# SeparationPCB.net
KiCad netlist of a schematic drawn in EAGLE
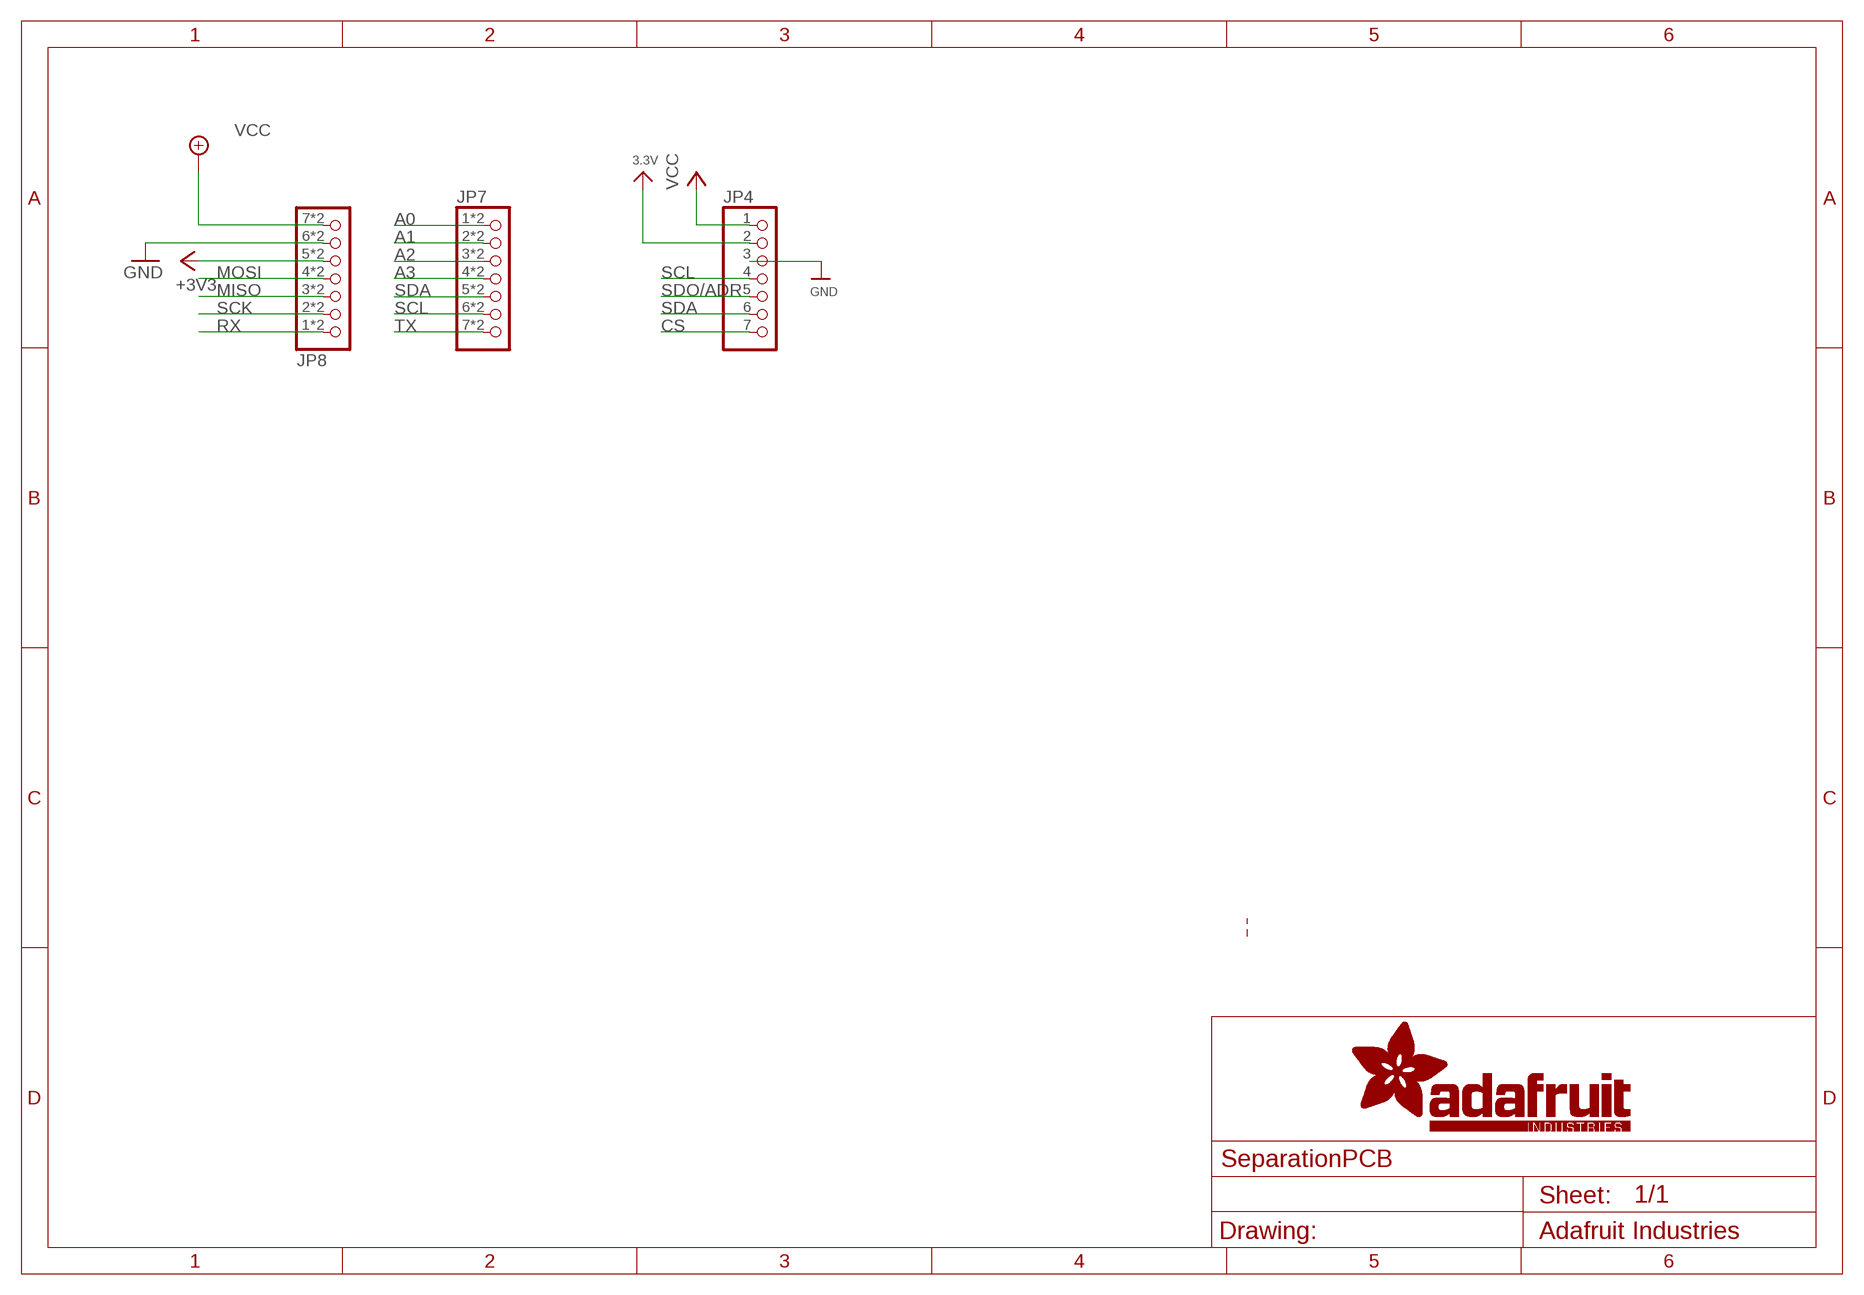
[diagram p0: schematic, sheet 1]

(export (version "E")
  (design (tool "Eeschema 10.0.6"))
  (components
    (comp (ref "JP4")
      (value "HEADER-1X770MIL")
      (footprint "eagle-import:1X07_ROUND_70")
      (libsource (lib "eagle-import") (part "HEADER-1X770MIL"))
    )
    (comp (ref "JP7")
      (value "HEADER-1X7_CASTEL")
      (footprint "eagle-import:1X07_CASTEL")
      (libsource (lib "eagle-import") (part "HEADER-1X7_CASTEL"))
    )
    (comp (ref "JP8")
      (value "HEADER-1X7_CASTEL")
      (footprint "eagle-import:1X07_CASTEL")
      (libsource (lib "eagle-import") (part "HEADER-1X7_CASTEL"))
    )
  )
  (nets
    (net (code "1") (name "+3V3") (class "Default")
      (node (ref "JP8") (pin "5") (pinfunction "5_5") (pintype "passive"))
      (node (ref "JP8") (pin "5C") (pinfunction "5_5C") (pintype "passive"))
    )
    (net (code "2") (name "+5V") (class "Default")
      (node (ref "JP4") (pin "1") (pinfunction "1_1") (pintype "passive"))
      (node (ref "JP8") (pin "7") (pinfunction "7_7") (pintype "passive"))
      (node (ref "JP8") (pin "7C") (pinfunction "7_7C") (pintype "passive"))
    )
    (net (code "3") (name "/A0") (class "Default")
      (node (ref "JP7") (pin "1") (pinfunction "1_1") (pintype "passive"))
      (node (ref "JP7") (pin "1C") (pinfunction "1_1C") (pintype "passive"))
    )
    (net (code "4") (name "/A1") (class "Default")
      (node (ref "JP7") (pin "2") (pinfunction "2_2") (pintype "passive"))
      (node (ref "JP7") (pin "2C") (pinfunction "2_2C") (pintype "passive"))
    )
    (net (code "5") (name "/A2") (class "Default")
      (node (ref "JP7") (pin "3") (pinfunction "3_3") (pintype "passive"))
      (node (ref "JP7") (pin "3C") (pinfunction "3_3C") (pintype "passive"))
    )
    (net (code "6") (name "/A3") (class "Default")
      (node (ref "JP7") (pin "4") (pinfunction "4_4") (pintype "passive"))
      (node (ref "JP7") (pin "4C") (pinfunction "4_4C") (pintype "passive"))
    )
    (net (code "7") (name "/CS") (class "Default")
      (node (ref "JP4") (pin "7") (pinfunction "7_7") (pintype "passive"))
    )
    (net (code "8") (name "/MISO") (class "Default")
      (node (ref "JP8") (pin "3") (pinfunction "3_3") (pintype "passive"))
      (node (ref "JP8") (pin "3C") (pinfunction "3_3C") (pintype "passive"))
    )
    (net (code "9") (name "/MOSI") (class "Default")
      (node (ref "JP8") (pin "4") (pinfunction "4_4") (pintype "passive"))
      (node (ref "JP8") (pin "4C") (pinfunction "4_4C") (pintype "passive"))
    )
    (net (code "10") (name "/RX") (class "Default")
      (node (ref "JP8") (pin "1") (pinfunction "1_1") (pintype "passive"))
      (node (ref "JP8") (pin "1C") (pinfunction "1_1C") (pintype "passive"))
    )
    (net (code "11") (name "/SCK") (class "Default")
      (node (ref "JP8") (pin "2") (pinfunction "2_2") (pintype "passive"))
      (node (ref "JP8") (pin "2C") (pinfunction "2_2C") (pintype "passive"))
    )
    (net (code "12") (name "/SCL") (class "Default")
      (node (ref "JP4") (pin "4") (pinfunction "4_4") (pintype "passive"))
      (node (ref "JP7") (pin "6") (pinfunction "6_6") (pintype "passive"))
      (node (ref "JP7") (pin "6C") (pinfunction "6_6C") (pintype "passive"))
    )
    (net (code "13") (name "/SDA") (class "Default")
      (node (ref "JP4") (pin "6") (pinfunction "6_6") (pintype "passive"))
      (node (ref "JP7") (pin "5") (pinfunction "5_5") (pintype "passive"))
      (node (ref "JP7") (pin "5C") (pinfunction "5_5C") (pintype "passive"))
    )
    (net (code "14") (name "/SDO{slash}ADR") (class "Default")
      (node (ref "JP4") (pin "5") (pinfunction "5_5") (pintype "passive"))
    )
    (net (code "15") (name "/TX") (class "Default")
      (node (ref "JP7") (pin "7") (pinfunction "7_7") (pintype "passive"))
      (node (ref "JP7") (pin "7C") (pinfunction "7_7C") (pintype "passive"))
    )
    (net (code "16") (name "3.3V") (class "Default")
      (node (ref "JP4") (pin "2") (pinfunction "2_2") (pintype "passive"))
    )
    (net (code "17") (name "GND") (class "Default")
      (node (ref "JP4") (pin "3") (pinfunction "3_3") (pintype "passive"))
      (node (ref "JP8") (pin "6") (pinfunction "6_6") (pintype "passive"))
      (node (ref "JP8") (pin "6C") (pinfunction "6_6C") (pintype "passive"))
    )
  )
)
